# quadcopter.net
KiCad netlist of a schematic drawn in EAGLE
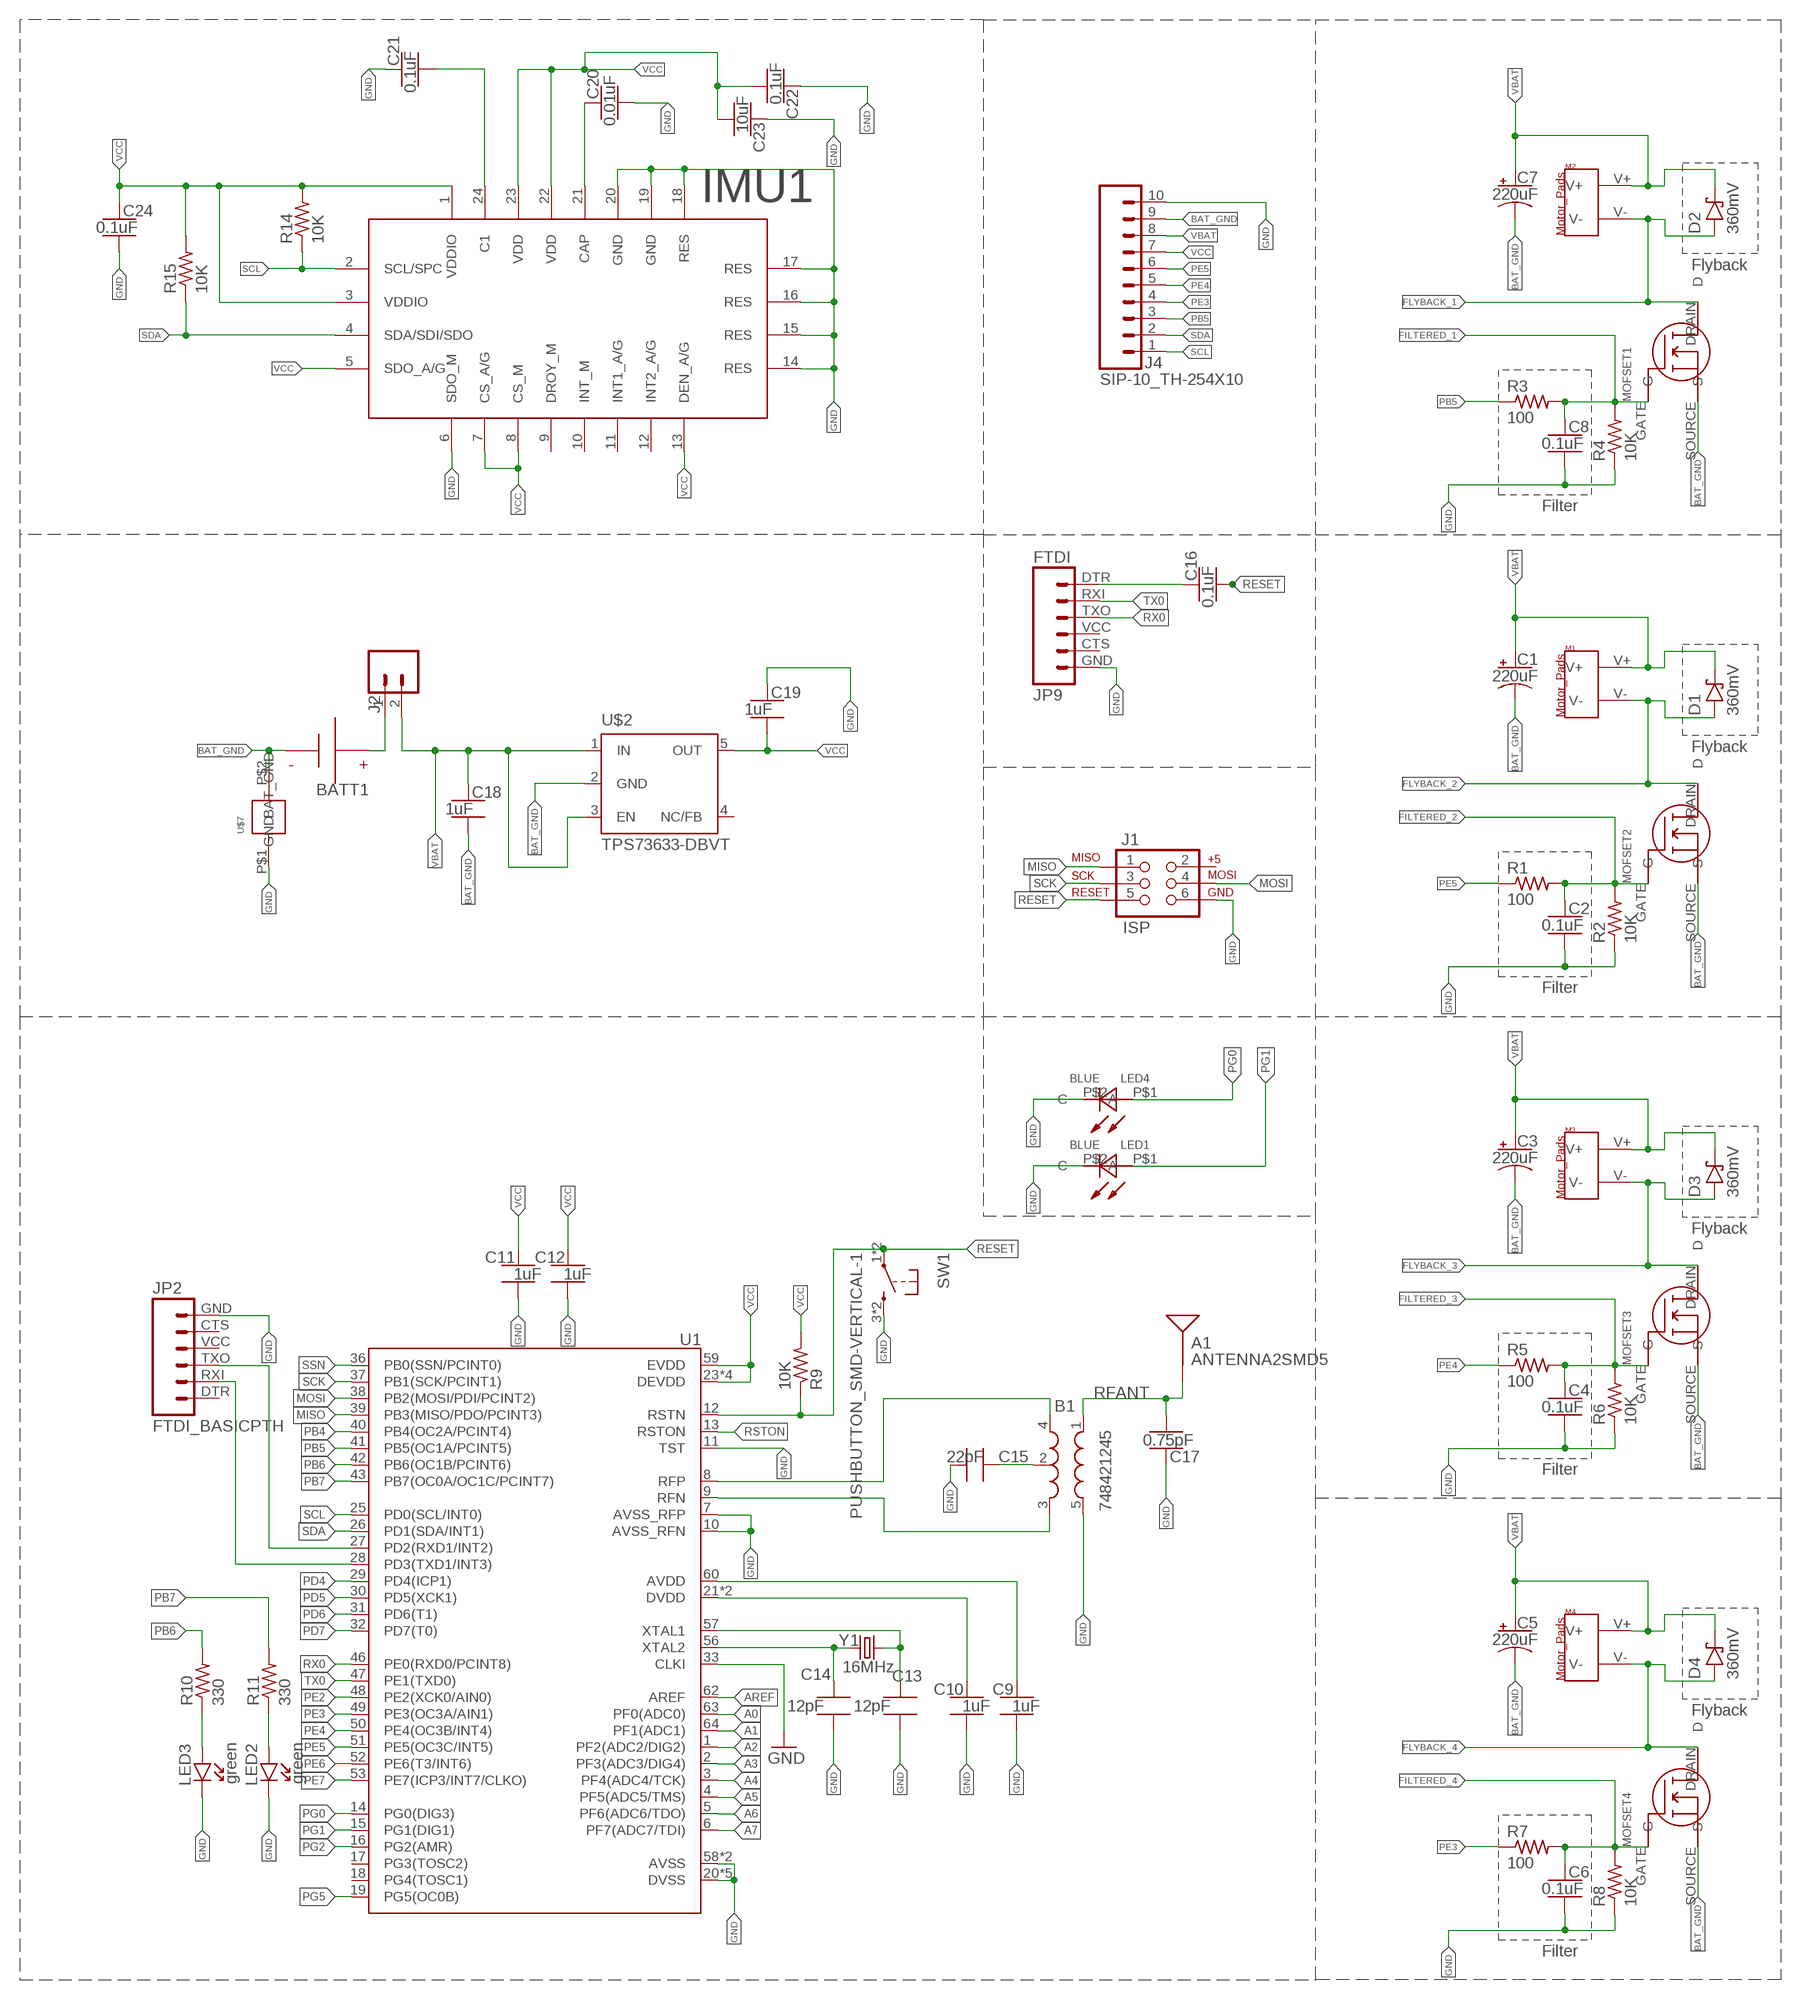
[diagram p0: schematic, sheet 1]

(export (version "E")
  (design (tool "Eeschema 10.0.6"))
  (components
    (comp (ref "A1")
      (value "ANTENNA2SMD5")
      (footprint "eagle-import:ANTENNA-CHIP5")
      (fields (field (name "MFR") "Linx Technologies Inc.") (field (name "MPN") "ANT-2.45-CHP-T"))
      (libsource (lib "eagle-import") (part "ANTENNA2SMD5"))
    )
    (comp (ref "B1")
      (value "748421245")
      (footprint "eagle-import:BALUN")
      (fields (field (name "MFR") "Wurth Electronics Inc") (field (name "CREATOR") "PROF"))
      (libsource (lib "eagle-import") (part "BALUN0805"))
    )
    (comp (ref "BATT1")
      (value "BATTERY-HUBSAN-W/HOLDER")
      (footprint "eagle-import:BATTERY-W_HOLDER-380MAH-HUBSAN")
      (fields
        (field (name "MFR") "HUBSAN")
        (field (name "MPN") "X4-H107C-8-in-1")
        (field (name "CREATOR") "Swanson")
      )
      (libsource (lib "eagle-import") (part "BATTERY-HUBSAN-W/HOLDER"))
    )
    (comp (ref "C1")
      (value "220uF")
      (footprint "eagle-import:CAPMP7343X310_HS")
      (fields (field (name "MFR") "AVX Corporation") (field (name "MPN") "TAJD227K006RNJ"))
      (libsource (lib "eagle-import") (part "CAPACITOR-POL_SMD-7043-D_TANTALUM-220UF"))
    )
    (comp (ref "C2")
      (value "0.1uF")
      (footprint "eagle-import:CAPC2012X140_HS")
      (fields
        (field (name "MFR") "Murata Electronics North America")
        (field (name "MPN") "GRM21BR71H104KA01L")
        (field (name "CREATOR") "PROF")
      )
      (libsource (lib "eagle-import") (part "CAPACITOR-NP_SMD-2012-0805_CERAMIC-0.1UF"))
    )
    (comp (ref "C3")
      (value "220uF")
      (footprint "eagle-import:CAPMP7343X310_HS")
      (fields (field (name "MFR") "AVX Corporation") (field (name "MPN") "TAJD227K006RNJ"))
      (libsource (lib "eagle-import") (part "CAPACITOR-POL_SMD-7043-D_TANTALUM-220UF"))
    )
    (comp (ref "C4")
      (value "0.1uF")
      (footprint "eagle-import:CAPC2012X140_HS")
      (fields
        (field (name "MFR") "Murata Electronics North America")
        (field (name "MPN") "GRM21BR71H104KA01L")
        (field (name "CREATOR") "PROF")
      )
      (libsource (lib "eagle-import") (part "CAPACITOR-NP_SMD-2012-0805_CERAMIC-0.1UF"))
    )
    (comp (ref "C5")
      (value "220uF")
      (footprint "eagle-import:CAPMP7343X310_HS")
      (fields (field (name "MFR") "AVX Corporation") (field (name "MPN") "TAJD227K006RNJ"))
      (libsource (lib "eagle-import") (part "CAPACITOR-POL_SMD-7043-D_TANTALUM-220UF"))
    )
    (comp (ref "C6")
      (value "0.1uF")
      (footprint "eagle-import:CAPC2012X140_HS")
      (fields
        (field (name "MFR") "Murata Electronics North America")
        (field (name "MPN") "GRM21BR71H104KA01L")
        (field (name "CREATOR") "PROF")
      )
      (libsource (lib "eagle-import") (part "CAPACITOR-NP_SMD-2012-0805_CERAMIC-0.1UF"))
    )
    (comp (ref "C7")
      (value "220uF")
      (footprint "eagle-import:CAPMP7343X310_HS")
      (fields (field (name "MFR") "AVX Corporation") (field (name "MPN") "TAJD227K006RNJ"))
      (libsource (lib "eagle-import") (part "CAPACITOR-POL_SMD-7043-D_TANTALUM-220UF"))
    )
    (comp (ref "C8")
      (value "0.1uF")
      (footprint "eagle-import:CAPC2012X140_HS")
      (fields
        (field (name "MFR") "Murata Electronics North America")
        (field (name "MPN") "GRM21BR71H104KA01L")
        (field (name "CREATOR") "PROF")
      )
      (libsource (lib "eagle-import") (part "CAPACITOR-NP_SMD-2012-0805_CERAMIC-0.1UF"))
    )
    (comp (ref "C9")
      (value "1uF")
      (footprint "eagle-import:CAPC2012X140_HS")
      (fields
        (field (name "MFR") "Murata Electronics North America")
        (field (name "MPN") "GRM21BR71H105KA12L")
      )
      (libsource (lib "eagle-import") (part "CAPACITOR-NP_SMD-2012-0805_CERAMIC-1UF"))
    )
    (comp (ref "C10")
      (value "1uF")
      (footprint "eagle-import:CAPC2012X140_HS")
      (fields
        (field (name "MFR") "Murata Electronics North America")
        (field (name "MPN") "GRM21BR71H105KA12L")
      )
      (libsource (lib "eagle-import") (part "CAPACITOR-NP_SMD-2012-0805_CERAMIC-1UF"))
    )
    (comp (ref "C11")
      (value "1uF")
      (footprint "eagle-import:CAPC2012X140_HS")
      (fields
        (field (name "MFR") "Murata Electronics North America")
        (field (name "MPN") "GRM21BR71H105KA12L")
      )
      (libsource (lib "eagle-import") (part "CAPACITOR-NP_SMD-2012-0805_CERAMIC-1UF"))
    )
    (comp (ref "C12")
      (value "1uF")
      (footprint "eagle-import:CAPC2012X140_HS")
      (fields
        (field (name "MFR") "Murata Electronics North America")
        (field (name "MPN") "GRM21BR71H105KA12L")
      )
      (libsource (lib "eagle-import") (part "CAPACITOR-NP_SMD-2012-0805_CERAMIC-1UF"))
    )
    (comp (ref "C13")
      (value "12pF")
      (footprint "eagle-import:CAPC2012X140_HS")
      (fields
        (field (name "MFR") "Murata Electronics North America")
        (field (name "MPN") "GRM21A5C2E120JW01D")
      )
      (libsource (lib "eagle-import") (part "CAPACITOR-NP_SMD-2012-0805_CERAMIC-12PF"))
    )
    (comp (ref "C14")
      (value "12pF")
      (footprint "eagle-import:CAPC2012X140_HS")
      (fields
        (field (name "MFR") "Murata Electronics North America")
        (field (name "MPN") "GRM21A5C2E120JW01D")
      )
      (libsource (lib "eagle-import") (part "CAPACITOR-NP_SMD-2012-0805_CERAMIC-12PF"))
    )
    (comp (ref "C15")
      (value "22pF")
      (footprint "eagle-import:CAPC2012X140_HS")
      (fields
        (field (name "MFR") "Murata Electronics North America")
        (field (name "MPN") "GRM21A5C2E220JW01D")
        (field (name "CREATOR") "PROF")
      )
      (libsource (lib "eagle-import") (part "CAPACITOR-NP_SMD-2012-0805_CERAMIC-22PF"))
    )
    (comp (ref "C16")
      (value "0.1uF")
      (footprint "eagle-import:CAPC2012X140_HS")
      (fields
        (field (name "MFR") "Murata Electronics North America")
        (field (name "MPN") "GRM21BR71H104KA01L")
        (field (name "CREATOR") "PROF")
      )
      (libsource (lib "eagle-import") (part "CAPACITOR-NP_SMD-2012-0805_CERAMIC-0.1UF"))
    )
    (comp (ref "C17")
      (value "0.75pF")
      (footprint "eagle-import:CAPC2012X140_HS")
      (fields
        (field (name "MFR") "Murata Electronics North America")
        (field (name "MPN") "GQM2195C2AR75CB01D")
      )
      (libsource (lib "eagle-import") (part "CAPACITOR-NP_SMD-2012-0805_CERAMIC-0.75PF"))
    )
    (comp (ref "C18")
      (value "1uF")
      (footprint "eagle-import:CAPC2012X140_HS")
      (fields
        (field (name "MFR") "Murata Electronics North America")
        (field (name "MPN") "GRM21BR71H105KA12L")
      )
      (libsource (lib "eagle-import") (part "CAPACITOR-NP_SMD-2012-0805_CERAMIC-1UF"))
    )
    (comp (ref "C19")
      (value "1uF")
      (footprint "eagle-import:CAPC2012X140_HS")
      (fields
        (field (name "MFR") "Murata Electronics North America")
        (field (name "MPN") "GRM21BR71H105KA12L")
      )
      (libsource (lib "eagle-import") (part "CAPACITOR-NP_SMD-2012-0805_CERAMIC-1UF"))
    )
    (comp (ref "C20")
      (value "0.01uF")
      (footprint "eagle-import:CAPC2012X140_HS")
      (fields
        (field (name "MFR") "Murata Electronics North America")
        (field (name "MPN") "GRM2195C1H103FA01D")
        (field (name "CREATOR") "PROF")
      )
      (libsource (lib "eagle-import") (part "CAPACITOR-NP_SMD-2012-0805_CERAMIC-0.01UF"))
    )
    (comp (ref "C21")
      (value "0.1uF")
      (footprint "eagle-import:CAPC2012X140_HS")
      (fields
        (field (name "MFR") "Murata Electronics North America")
        (field (name "MPN") "GRM21BR71H104KA01L")
        (field (name "CREATOR") "PROF")
      )
      (libsource (lib "eagle-import") (part "CAPACITOR-NP_SMD-2012-0805_CERAMIC-0.1UF"))
    )
    (comp (ref "C22")
      (value "0.1uF")
      (footprint "eagle-import:CAPC2012X140_HS")
      (fields
        (field (name "MFR") "Murata Electronics North America")
        (field (name "MPN") "GRM21BR71H104KA01L")
        (field (name "CREATOR") "PROF")
      )
      (libsource (lib "eagle-import") (part "CAPACITOR-NP_SMD-2012-0805_CERAMIC-0.1UF"))
    )
    (comp (ref "C23")
      (value "10uF")
      (footprint "eagle-import:CAPC2012X140_HS")
      (fields
        (field (name "MFR") "Murata Electronics North America")
        (field (name "MPN") "GRM21BR61E106KA73L")
      )
      (libsource (lib "eagle-import") (part "CAPACITOR-NP_SMD-2012-0805_CERAMIC-10UF"))
    )
    (comp (ref "C24")
      (value "0.1uF")
      (footprint "eagle-import:CAPC2012X140_HS")
      (fields
        (field (name "MFR") "Murata Electronics North America")
        (field (name "MPN") "GRM21BR71H104KA01L")
        (field (name "CREATOR") "PROF")
      )
      (libsource (lib "eagle-import") (part "CAPACITOR-NP_SMD-2012-0805_CERAMIC-0.1UF"))
    )
    (comp (ref "D1")
      (value "360mV")
      (footprint "eagle-import:SOD3716X135_HS")
      (fields
        (field (name "MFR") "Toshiba Semiconductor and Storage")
        (field (name "MPN") "CRS08(TE85L,Q,M)")
      )
      (libsource (lib "eagle-import") (part "DIODE-SCHOTTKY_SMD-SOD123-360MV"))
    )
    (comp (ref "D2")
      (value "360mV")
      (footprint "eagle-import:SOD3716X135_HS")
      (fields
        (field (name "MFR") "Toshiba Semiconductor and Storage")
        (field (name "MPN") "CRS08(TE85L,Q,M)")
      )
      (libsource (lib "eagle-import") (part "DIODE-SCHOTTKY_SMD-SOD123-360MV"))
    )
    (comp (ref "D3")
      (value "360mV")
      (footprint "eagle-import:SOD3716X135_HS")
      (fields
        (field (name "MFR") "Toshiba Semiconductor and Storage")
        (field (name "MPN") "CRS08(TE85L,Q,M)")
      )
      (libsource (lib "eagle-import") (part "DIODE-SCHOTTKY_SMD-SOD123-360MV"))
    )
    (comp (ref "D4")
      (value "360mV")
      (footprint "eagle-import:SOD3716X135_HS")
      (fields
        (field (name "MFR") "Toshiba Semiconductor and Storage")
        (field (name "MPN") "CRS08(TE85L,Q,M)")
      )
      (libsource (lib "eagle-import") (part "DIODE-SCHOTTKY_SMD-SOD123-360MV"))
    )
    (comp (ref "IMU1")
      (value "9_AXIS_IMU")
      (footprint "eagle-import:9_AXIS_IMU")
      (fields
        (field (name "MFR") "STMicroelectronics")
        (field (name "MPN") "LSM9DS1TR")
        (field (name "CREATOR") "Yupei")
        (field (name "REVIEWER") "Group 9")
      )
      (libsource (lib "eagle-import") (part "9_AXIS_IMU"))
    )
    (comp (ref "J1")
      (value "ISP")
      (footprint "eagle-import:2X3-NS")
      (fields
        (field (name "MFR") "Amphenol FCI")
        (field (name "MPN") "67997-206HLF")
        (field (name "CREATOR") "PROF")
      )
      (libsource (lib "eagle-import") (part "AVR_SPI_PRG_6NS"))
    )
    (comp (ref "J2")
      (value "MALE_HEADER_2POS-2X1-0.1IN")
      (footprint "eagle-import:MALE_HEADER_2X1_0.1IN")
      (fields
        (field (name "MFR") "3M")
        (field (name "MPN") "961102-6404-AR")
        (field (name "CREATOR") "SWANSON")
        (field (name "REVIEWER") "Group 9")
      )
      (libsource (lib "eagle-import") (part "MALE_HEADER_2POS-2X1-0.1IN"))
    )
    (comp (ref "J4")
      (value "SIP-10_TH-254X10")
      (footprint "eagle-import:HDRV10W63P254_10X1_2540X254H838_HS")
      (fields (field (name "MFR") "Amphenol FCI") (field (name "MPN") "68000-110HLF"))
      (libsource (lib "eagle-import") (part "SIP-10_TH-254X10"))
    )
    (comp (ref "JP2")
      (value "FTDI_BASICPTH")
      (footprint "eagle-import:FTDI_BASIC")
      (fields (field (name "MFR") "Amphenol FCI") (field (name "MPN") "68016-406HLF"))
      (libsource (lib "eagle-import") (part "FTDI_BASICPTH"))
    )
    (comp (ref "JP9")
      (value "FTDI")
      (footprint "eagle-import:FTDI_BASIC")
      (fields (field (name "MFR") "Amphenol FCI") (field (name "MPN") "68016-406HLF"))
      (libsource (lib "eagle-import") (part "FTDI_BASICPTH"))
    )
    (comp (ref "LED1")
      (value "BLUE")
      (footprint "eagle-import:CUT_TAPE")
      (fields
        (field (name "MFR") "Lite-On Inc ")
        (field (name "MPN") "LTST-C193TBKT-5A")
        (field (name "CREATOR") "Yueqi Wang")
        (field (name "REVIEWER") "Group 9")
      )
      (libsource (lib "eagle-import") (part "LTST-C193TBKT-5ADISCRETE_LED"))
    )
    (comp (ref "LED2")
      (value "green")
      (footprint "eagle-import:LEDSC125X200X120-2_HS")
      (fields (field (name "MFR") "Lite-On Inc") (field (name "MPN") "LTST-C170GKT"))
      (libsource (lib "eagle-import") (part "DIODE-LED_SMD-2012-0805-GREEN"))
    )
    (comp (ref "LED3")
      (value "green")
      (footprint "eagle-import:LEDSC125X200X120-2_HS")
      (fields (field (name "MFR") "Lite-On Inc") (field (name "MPN") "LTST-C170GKT"))
      (libsource (lib "eagle-import") (part "DIODE-LED_SMD-2012-0805-GREEN"))
    )
    (comp (ref "LED4")
      (value "BLUE")
      (footprint "eagle-import:CUT_TAPE")
      (fields
        (field (name "MFR") "Lite-On Inc ")
        (field (name "MPN") "LTST-C193TBKT-5A")
        (field (name "CREATOR") "Yueqi Wang")
        (field (name "REVIEWER") "Group 9")
      )
      (libsource (lib "eagle-import") (part "LTST-C193TBKT-5ADISCRETE_LED"))
    )
    (comp (ref "M1")
      (value "MOTOR_PADS")
      (footprint "eagle-import:MOTOR_PADS")
      (fields (field (name "MFR") "NA") (field (name "CREATOR") "PROF"))
      (libsource (lib "eagle-import") (part "MOTOR_PADS"))
    )
    (comp (ref "M2")
      (value "MOTOR_PADS")
      (footprint "eagle-import:MOTOR_PADS")
      (fields (field (name "MFR") "NA") (field (name "CREATOR") "PROF"))
      (libsource (lib "eagle-import") (part "MOTOR_PADS"))
    )
    (comp (ref "M3")
      (value "MOTOR_PADS")
      (footprint "eagle-import:MOTOR_PADS")
      (fields (field (name "MFR") "NA") (field (name "CREATOR") "PROF"))
      (libsource (lib "eagle-import") (part "MOTOR_PADS"))
    )
    (comp (ref "M4")
      (value "MOTOR_PADS")
      (footprint "eagle-import:MOTOR_PADS")
      (fields (field (name "MFR") "NA") (field (name "CREATOR") "PROF"))
      (libsource (lib "eagle-import") (part "MOTOR_PADS"))
    )
    (comp (ref "MOFSET1")
      (value "SI2302CDS_N_MOFSETSI2302CDS")
      (footprint "eagle-import:N-CHANNEL_MOSFET")
      (fields
        (field (name "MFR") "Vishay Siliconix ")
        (field (name "MPN") "SI2302CDS-T1-E3 ")
        (field (name "CREATOR") "YUEQI WANG")
        (field (name "REVIEWER") "Group 9")
      )
      (libsource (lib "eagle-import") (part "SI2302CDS_N_MOFSETSI2302CDS"))
    )
    (comp (ref "MOFSET2")
      (value "SI2302CDS_N_MOFSETSI2302CDS")
      (footprint "eagle-import:N-CHANNEL_MOSFET")
      (fields
        (field (name "MFR") "Vishay Siliconix ")
        (field (name "MPN") "SI2302CDS-T1-E3 ")
        (field (name "CREATOR") "YUEQI WANG")
        (field (name "REVIEWER") "Group 9")
      )
      (libsource (lib "eagle-import") (part "SI2302CDS_N_MOFSETSI2302CDS"))
    )
    (comp (ref "MOFSET3")
      (value "SI2302CDS_N_MOFSETSI2302CDS")
      (footprint "eagle-import:N-CHANNEL_MOSFET")
      (fields
        (field (name "MFR") "Vishay Siliconix ")
        (field (name "MPN") "SI2302CDS-T1-E3 ")
        (field (name "CREATOR") "YUEQI WANG")
        (field (name "REVIEWER") "Group 9")
      )
      (libsource (lib "eagle-import") (part "SI2302CDS_N_MOFSETSI2302CDS"))
    )
    (comp (ref "MOFSET4")
      (value "SI2302CDS_N_MOFSETSI2302CDS")
      (footprint "eagle-import:N-CHANNEL_MOSFET")
      (fields
        (field (name "MFR") "Vishay Siliconix ")
        (field (name "MPN") "SI2302CDS-T1-E3 ")
        (field (name "CREATOR") "YUEQI WANG")
        (field (name "REVIEWER") "Group 9")
      )
      (libsource (lib "eagle-import") (part "SI2302CDS_N_MOFSETSI2302CDS"))
    )
    (comp (ref "R1")
      (value "100")
      (footprint "eagle-import:RESC2012X60_HS")
      (fields
        (field (name "MFR") "Yageo")
        (field (name "MPN") "RC0805JR-07100RL")
        (field (name "CREATOR") "PROF")
      )
      (libsource (lib "eagle-import") (part "RESISTOR_SMD-2012-0805-100"))
    )
    (comp (ref "R2")
      (value "10K")
      (footprint "eagle-import:RESC2012X60_HS")
      (fields
        (field (name "MFR") "Yageo")
        (field (name "MPN") "RC0805JR-0710KL")
        (field (name "CREATOR") "PROF")
      )
      (libsource (lib "eagle-import") (part "RESISTOR_SMD-2012-0805-10K"))
    )
    (comp (ref "R3")
      (value "100")
      (footprint "eagle-import:RESC2012X60_HS")
      (fields
        (field (name "MFR") "Yageo")
        (field (name "MPN") "RC0805JR-07100RL")
        (field (name "CREATOR") "PROF")
      )
      (libsource (lib "eagle-import") (part "RESISTOR_SMD-2012-0805-100"))
    )
    (comp (ref "R4")
      (value "10K")
      (footprint "eagle-import:RESC2012X60_HS")
      (fields
        (field (name "MFR") "Yageo")
        (field (name "MPN") "RC0805JR-0710KL")
        (field (name "CREATOR") "PROF")
      )
      (libsource (lib "eagle-import") (part "RESISTOR_SMD-2012-0805-10K"))
    )
    (comp (ref "R5")
      (value "100")
      (footprint "eagle-import:RESC2012X60_HS")
      (fields
        (field (name "MFR") "Yageo")
        (field (name "MPN") "RC0805JR-07100RL")
        (field (name "CREATOR") "PROF")
      )
      (libsource (lib "eagle-import") (part "RESISTOR_SMD-2012-0805-100"))
    )
    (comp (ref "R6")
      (value "10K")
      (footprint "eagle-import:RESC2012X60_HS")
      (fields
        (field (name "MFR") "Yageo")
        (field (name "MPN") "RC0805JR-0710KL")
        (field (name "CREATOR") "PROF")
      )
      (libsource (lib "eagle-import") (part "RESISTOR_SMD-2012-0805-10K"))
    )
    (comp (ref "R7")
      (value "100")
      (footprint "eagle-import:RESC2012X60_HS")
      (fields
        (field (name "MFR") "Yageo")
        (field (name "MPN") "RC0805JR-07100RL")
        (field (name "CREATOR") "PROF")
      )
      (libsource (lib "eagle-import") (part "RESISTOR_SMD-2012-0805-100"))
    )
    (comp (ref "R8")
      (value "10K")
      (footprint "eagle-import:RESC2012X60_HS")
      (fields
        (field (name "MFR") "Yageo")
        (field (name "MPN") "RC0805JR-0710KL")
        (field (name "CREATOR") "PROF")
      )
      (libsource (lib "eagle-import") (part "RESISTOR_SMD-2012-0805-10K"))
    )
    (comp (ref "R9")
      (value "10K")
      (footprint "eagle-import:RESC2012X60_HS")
      (fields
        (field (name "MFR") "Yageo")
        (field (name "MPN") "RC0805JR-0710KL")
        (field (name "CREATOR") "PROF")
      )
      (libsource (lib "eagle-import") (part "RESISTOR_SMD-2012-0805-10K"))
    )
    (comp (ref "R10")
      (value "330")
      (footprint "eagle-import:RESC2012X60_HS")
      (fields
        (field (name "MFR") "Yageo")
        (field (name "MPN") "RC0805JR-07330RL")
        (field (name "CREATOR") "PROF")
      )
      (libsource (lib "eagle-import") (part "RESISTOR_SMD-2012-0805-330"))
    )
    (comp (ref "R11")
      (value "330")
      (footprint "eagle-import:RESC2012X60_HS")
      (fields
        (field (name "MFR") "Yageo")
        (field (name "MPN") "RC0805JR-07330RL")
        (field (name "CREATOR") "PROF")
      )
      (libsource (lib "eagle-import") (part "RESISTOR_SMD-2012-0805-330"))
    )
    (comp (ref "R14")
      (value "10K")
      (footprint "eagle-import:RESC2012X60_HS")
      (fields
        (field (name "MFR") "Yageo")
        (field (name "MPN") "RC0805JR-0710KL")
        (field (name "CREATOR") "PROF")
      )
      (libsource (lib "eagle-import") (part "RESISTOR_SMD-2012-0805-10K"))
    )
    (comp (ref "R15")
      (value "10K")
      (footprint "eagle-import:RESC2012X60_HS")
      (fields
        (field (name "MFR") "Yageo")
        (field (name "MPN") "RC0805JR-0710KL")
        (field (name "CREATOR") "PROF")
      )
      (libsource (lib "eagle-import") (part "RESISTOR_SMD-2012-0805-10K"))
    )
    (comp (ref "SW1")
      (value "PUSHBUTTON_SMD-VERTICAL-1")
      (footprint "eagle-import:TE_FSM8JSMA_HS")
      (fields (field (name "MFR") "TE Connectivity Alcoswitch Switches") (field (name "MPN") "FSM4JSMA"))
      (libsource (lib "eagle-import") (part "PUSHBUTTON_SMD-VERTICAL-1"))
    )
    (comp (ref "U$2")
      (value "TPS73633-DBVT")
      (footprint "eagle-import:SOT23-DBV")
      (fields (field (name "MFR") "Texas Instruments") (field (name "MPN") "LP3985IM5X-3.0/NOPB"))
      (libsource (lib "eagle-import") (part "TPS73633-DBVT"))
    )
    (comp (ref "U$7")
      (value "NET_BRIDGE")
      (footprint "eagle-import:NET_BRIDGE")
      (libsource (lib "eagle-import") (part "NET_BRIDGE"))
    )
    (comp (ref "U1")
      (value "ATMEGA128RFA1")
      (footprint "eagle-import:QFN-64")
      (fields
        (field (name "MFR") "Atmel")
        (field (name "MPN") "ATMEGA128RFA1-ZUR00")
        (field (name "CREATOR") "Swanson")
      )
      (libsource (lib "eagle-import") (part "ATMEGA128RFA1"))
    )
    (comp (ref "Y1")
      (value "16MHz")
      (footprint "eagle-import:CRYSTAL-SMD-5X3")
      (fields (field (name "MFR") "Abracon LLC") (field (name "MPN") "ABM3B-16.000MHZ-B2-T"))
      (libsource (lib "eagle-import") (part "CRYSTAL5X3"))
    )
  )
  (nets
    (net (code "1") (name "/RFANT") (class "Default")
      (node (ref "A1") (pin "FEED") (pinfunction "SIGNAL_FEED") (pintype "bidirectional"))
      (node (ref "B1") (pin "1") (pinfunction "IN_1") (pintype "bidirectional"))
      (node (ref "C17") (pin "2") (pinfunction "2_2") (pintype "passive"))
    )
    (net (code "2") (name "A0") (class "Default")
      (node (ref "U1") (pin "63") (pinfunction "PF0(ADC0)_63") (pintype "bidirectional"))
    )
    (net (code "3") (name "A1") (class "Default")
      (node (ref "U1") (pin "64") (pinfunction "PF1(ADC1)_64") (pintype "bidirectional"))
    )
    (net (code "4") (name "A2") (class "Default")
      (node (ref "U1") (pin "1") (pinfunction "PF2(ADC2/DIG2)_1") (pintype "bidirectional"))
    )
    (net (code "5") (name "A3") (class "Default")
      (node (ref "U1") (pin "2") (pinfunction "PF3(ADC3/DIG4)_2") (pintype "bidirectional"))
    )
    (net (code "6") (name "A4") (class "Default")
      (node (ref "U1") (pin "3") (pinfunction "PF4(ADC4/TCK)_3") (pintype "bidirectional"))
    )
    (net (code "7") (name "A5") (class "Default")
      (node (ref "U1") (pin "4") (pinfunction "PF5(ADC5/TMS)_4") (pintype "bidirectional"))
    )
    (net (code "8") (name "A6") (class "Default")
      (node (ref "U1") (pin "5") (pinfunction "PF6(ADC6/TDO)_5") (pintype "bidirectional"))
    )
    (net (code "9") (name "A7") (class "Default")
      (node (ref "U1") (pin "6") (pinfunction "PF7(ADC7/TDI)_6") (pintype "bidirectional"))
    )
    (net (code "10") (name "AREF") (class "Default")
      (node (ref "U1") (pin "62") (pinfunction "AREF_62") (pintype "bidirectional"))
    )
    (net (code "11") (name "BAT_GND") (class "Default")
      (node (ref "BATT1") (pin "-") (pinfunction "N_-") (pintype "bidirectional"))
      (node (ref "C1") (pin "2") (pinfunction "-_2") (pintype "passive"))
      (node (ref "C18") (pin "2") (pinfunction "2_2") (pintype "passive"))
      (node (ref "C3") (pin "2") (pinfunction "-_2") (pintype "passive"))
      (node (ref "C5") (pin "2") (pinfunction "-_2") (pintype "passive"))
      (node (ref "C7") (pin "2") (pinfunction "-_2") (pintype "passive"))
      (node (ref "J4") (pin "9") (pinfunction "9_9") (pintype "passive"))
      (node (ref "MOFSET1") (pin "SOURCE") (pinfunction "S_SOURCE") (pintype "bidirectional"))
      (node (ref "MOFSET2") (pin "SOURCE") (pinfunction "S_SOURCE") (pintype "bidirectional"))
      (node (ref "MOFSET3") (pin "SOURCE") (pinfunction "S_SOURCE") (pintype "bidirectional"))
      (node (ref "MOFSET4") (pin "SOURCE") (pinfunction "S_SOURCE") (pintype "bidirectional"))
      (node (ref "U$2") (pin "2") (pinfunction "GND_2") (pintype "input"))
      (node (ref "U$7") (pin "P$2") (pinfunction "GND_P$2") (pintype "bidirectional"))
    )
    (net (code "12") (name "FILTERED_1") (class "Default")
      (node (ref "C8") (pin "1") (pinfunction "1_1") (pintype "passive"))
      (node (ref "MOFSET1") (pin "GATE") (pinfunction "G_GATE") (pintype "bidirectional"))
      (node (ref "R3") (pin "2") (pinfunction "2_2") (pintype "passive"))
      (node (ref "R4") (pin "2") (pinfunction "2_2") (pintype "passive"))
    )
    (net (code "13") (name "FILTERED_2") (class "Default")
      (node (ref "C2") (pin "1") (pinfunction "1_1") (pintype "passive"))
      (node (ref "MOFSET2") (pin "GATE") (pinfunction "G_GATE") (pintype "bidirectional"))
      (node (ref "R1") (pin "2") (pinfunction "2_2") (pintype "passive"))
      (node (ref "R2") (pin "2") (pinfunction "2_2") (pintype "passive"))
    )
    (net (code "14") (name "FILTERED_3") (class "Default")
      (node (ref "C4") (pin "1") (pinfunction "1_1") (pintype "passive"))
      (node (ref "MOFSET3") (pin "GATE") (pinfunction "G_GATE") (pintype "bidirectional"))
      (node (ref "R5") (pin "2") (pinfunction "2_2") (pintype "passive"))
      (node (ref "R6") (pin "2") (pinfunction "2_2") (pintype "passive"))
    )
    (net (code "15") (name "FILTERED_4") (class "Default")
      (node (ref "C6") (pin "1") (pinfunction "1_1") (pintype "passive"))
      (node (ref "MOFSET4") (pin "GATE") (pinfunction "G_GATE") (pintype "bidirectional"))
      (node (ref "R7") (pin "2") (pinfunction "2_2") (pintype "passive"))
      (node (ref "R8") (pin "2") (pinfunction "2_2") (pintype "passive"))
    )
    (net (code "16") (name "FLYBACK_1") (class "Default")
      (node (ref "D2") (pin "A") (pinfunction "A_A") (pintype "passive"))
      (node (ref "M2") (pin "V-") (pinfunction "V-_V-") (pintype "bidirectional"))
      (node (ref "MOFSET1") (pin "DRAIN") (pinfunction "D_DRAIN") (pintype "bidirectional"))
    )
    (net (code "17") (name "FLYBACK_2") (class "Default")
      (node (ref "D1") (pin "A") (pinfunction "A_A") (pintype "passive"))
      (node (ref "M1") (pin "V-") (pinfunction "V-_V-") (pintype "bidirectional"))
      (node (ref "MOFSET2") (pin "DRAIN") (pinfunction "D_DRAIN") (pintype "bidirectional"))
    )
    (net (code "18") (name "FLYBACK_3") (class "Default")
      (node (ref "D3") (pin "A") (pinfunction "A_A") (pintype "passive"))
      (node (ref "M3") (pin "V-") (pinfunction "V-_V-") (pintype "bidirectional"))
      (node (ref "MOFSET3") (pin "DRAIN") (pinfunction "D_DRAIN") (pintype "bidirectional"))
    )
    (net (code "19") (name "FLYBACK_4") (class "Default")
      (node (ref "D4") (pin "A") (pinfunction "A_A") (pintype "passive"))
      (node (ref "M4") (pin "V-") (pinfunction "V-_V-") (pintype "bidirectional"))
      (node (ref "MOFSET4") (pin "DRAIN") (pinfunction "D_DRAIN") (pintype "bidirectional"))
    )
    (net (code "20") (name "GND") (class "Default")
      (node (ref "B1") (pin "5") (pinfunction "GND_5") (pintype "bidirectional"))
      (node (ref "C10") (pin "2") (pinfunction "2_2") (pintype "passive"))
      (node (ref "C11") (pin "2") (pinfunction "2_2") (pintype "passive"))
      (node (ref "C12") (pin "2") (pinfunction "2_2") (pintype "passive"))
      (node (ref "C13") (pin "2") (pinfunction "2_2") (pintype "passive"))
      (node (ref "C14") (pin "2") (pinfunction "2_2") (pintype "passive"))
      (node (ref "C15") (pin "2") (pinfunction "2_2") (pintype "passive"))
      (node (ref "C17") (pin "1") (pinfunction "1_1") (pintype "passive"))
      (node (ref "C19") (pin "1") (pinfunction "1_1") (pintype "passive"))
      (node (ref "C2") (pin "2") (pinfunction "2_2") (pintype "passive"))
      (node (ref "C20") (pin "2") (pinfunction "2_2") (pintype "passive"))
      (node (ref "C21") (pin "1") (pinfunction "1_1") (pintype "passive"))
      (node (ref "C22") (pin "1") (pinfunction "1_1") (pintype "passive"))
      (node (ref "C23") (pin "1") (pinfunction "1_1") (pintype "passive"))
      (node (ref "C24") (pin "2") (pinfunction "2_2") (pintype "passive"))
      (node (ref "C4") (pin "2") (pinfunction "2_2") (pintype "passive"))
      (node (ref "C6") (pin "2") (pinfunction "2_2") (pintype "passive"))
      (node (ref "C8") (pin "2") (pinfunction "2_2") (pintype "passive"))
      (node (ref "C9") (pin "2") (pinfunction "2_2") (pintype "passive"))
      (node (ref "IMU1") (pin "14") (pinfunction "RES_14") (pintype "bidirectional"))
      (node (ref "IMU1") (pin "15") (pinfunction "RES_15") (pintype "bidirectional"))
      (node (ref "IMU1") (pin "16") (pinfunction "RES_16") (pintype "bidirectional"))
      (node (ref "IMU1") (pin "17") (pinfunction "RES_17") (pintype "bidirectional"))
      (node (ref "IMU1") (pin "18") (pinfunction "RES_18") (pintype "bidirectional"))
      (node (ref "IMU1") (pin "19") (pinfunction "GND_19") (pintype "bidirectional"))
      (node (ref "IMU1") (pin "20") (pinfunction "GND_20") (pintype "bidirectional"))
      (node (ref "IMU1") (pin "6") (pinfunction "SDO_M_6") (pintype "bidirectional"))
      (node (ref "J1") (pin "6") (pinfunction "6_6") (pintype "passive"))
      (node (ref "J4") (pin "10") (pinfunction "10_10") (pintype "passive"))
      (node (ref "JP2") (pin "GND") (pinfunction "6_GND") (pintype "passive"))
      (node (ref "JP9") (pin "GND") (pinfunction "6_GND") (pintype "passive"))
      (node (ref "LED1") (pin "P$2") (pinfunction "C_P$2") (pintype "bidirectional"))
      (node (ref "LED2") (pin "C") (pinfunction "C_C") (pintype "passive"))
      (node (ref "LED3") (pin "C") (pinfunction "C_C") (pintype "passive"))
      (node (ref "LED4") (pin "P$2") (pinfunction "C_P$2") (pintype "bidirectional"))
      (node (ref "R2") (pin "1") (pinfunction "1_1") (pintype "passive"))
      (node (ref "R4") (pin "1") (pinfunction "1_1") (pintype "passive"))
      (node (ref "R6") (pin "1") (pinfunction "1_1") (pintype "passive"))
      (node (ref "R8") (pin "1") (pinfunction "1_1") (pintype "passive"))
      (node (ref "SW1") (pin "3") (pinfunction "2_3") (pintype "passive"))
      (node (ref "SW1") (pin "4") (pinfunction "2_4") (pintype "passive"))
      (node (ref "U$7") (pin "P$1") (pinfunction "BAT_GND_P$1") (pintype "bidirectional"))
      (node (ref "U1") (pin "10") (pinfunction "AVSS_RFN_10") (pintype "bidirectional"))
      (node (ref "U1") (pin "11") (pinfunction "TST_11") (pintype "bidirectional"))
      (node (ref "U1") (pin "20") (pinfunction "DVSS_20") (pintype "bidirectional"))
      (node (ref "U1") (pin "24") (pinfunction "DVSS_24") (pintype "bidirectional"))
      (node (ref "U1") (pin "33") (pinfunction "CLKI_33") (pintype "bidirectional"))
      (node (ref "U1") (pin "35") (pinfunction "DVSS_35") (pintype "bidirectional"))
      (node (ref "U1") (pin "45") (pinfunction "DVSS_45") (pintype "bidirectional"))
      (node (ref "U1") (pin "55") (pinfunction "DVSS_55") (pintype "bidirectional"))
      (node (ref "U1") (pin "58") (pinfunction "AVSS_58") (pintype "bidirectional"))
      (node (ref "U1") (pin "61") (pinfunction "AVSS_61") (pintype "bidirectional"))
      (node (ref "U1") (pin "7") (pinfunction "AVSS_RFP_7") (pintype "bidirectional"))
    )
    (net (code "21") (name "MISO") (class "Default")
      (node (ref "J1") (pin "1") (pinfunction "1_1") (pintype "passive"))
      (node (ref "U1") (pin "39") (pinfunction "PB3(MISO/PDO/PCINT3)_39") (pintype "bidirectional"))
    )
    (net (code "22") (name "MOSI") (class "Default")
      (node (ref "J1") (pin "4") (pinfunction "4_4") (pintype "passive"))
      (node (ref "U1") (pin "38") (pinfunction "PB2(MOSI/PDI/PCINT2)_38") (pintype "bidirectional"))
    )
    (net (code "23") (name "Net-(B1-GND-Pad2)") (class "Default")
      (node (ref "B1") (pin "2") (pinfunction "GND_2") (pintype "bidirectional"))
      (node (ref "C15") (pin "1") (pinfunction "1_1") (pintype "passive"))
    )
    (net (code "24") (name "Net-(B1-OUT1)") (class "Default")
      (node (ref "B1") (pin "4") (pinfunction "OUT1_4") (pintype "bidirectional"))
      (node (ref "U1") (pin "8") (pinfunction "RFP_8") (pintype "bidirectional"))
    )
    (net (code "25") (name "Net-(B1-OUT2)") (class "Default")
      (node (ref "B1") (pin "3") (pinfunction "OUT2_3") (pintype "bidirectional"))
      (node (ref "U1") (pin "9") (pinfunction "RFN_9") (pintype "bidirectional"))
    )
    (net (code "26") (name "Net-(BATT1-P)") (class "Default")
      (node (ref "BATT1") (pin "+") (pinfunction "P_+") (pintype "bidirectional"))
      (node (ref "J2") (pin "1") (pinfunction "1_1") (pintype "passive"))
    )
    (net (code "27") (name "Net-(C10-Pad1)") (class "Default")
      (node (ref "C10") (pin "1") (pinfunction "1_1") (pintype "passive"))
      (node (ref "U1") (pin "21") (pinfunction "DVDD_21") (pintype "bidirectional"))
      (node (ref "U1") (pin "22") (pinfunction "DVDD_22") (pintype "bidirectional"))
    )
    (net (code "28") (name "Net-(IMU1-C1)") (class "Default")
      (node (ref "C21") (pin "2") (pinfunction "2_2") (pintype "passive"))
      (node (ref "IMU1") (pin "24") (pinfunction "C1_24") (pintype "bidirectional"))
    )
    (net (code "29") (name "Net-(IMU1-CAP)") (class "Default")
      (node (ref "C20") (pin "1") (pinfunction "1_1") (pintype "passive"))
      (node (ref "IMU1") (pin "21") (pinfunction "CAP_21") (pintype "bidirectional"))
    )
    (net (code "30") (name "Net-(JP2-2)") (class "Default")
      (node (ref "JP2") (pin "RXI") (pinfunction "2_RXI") (pintype "passive"))
      (node (ref "U1") (pin "28") (pinfunction "PD3(TXD1/INT3)_28") (pintype "bidirectional"))
    )
    (net (code "31") (name "Net-(JP2-3)") (class "Default")
      (node (ref "JP2") (pin "TXO") (pinfunction "3_TXO") (pintype "passive"))
      (node (ref "U1") (pin "27") (pinfunction "PD2(RXD1/INT2)_27") (pintype "bidirectional"))
    )
    (net (code "32") (name "Net-(JP9-1)") (class "Default")
      (node (ref "C16") (pin "1") (pinfunction "1_1") (pintype "passive"))
      (node (ref "JP9") (pin "DTR") (pinfunction "1_DTR") (pintype "passive"))
    )
    (net (code "33") (name "Net-(LED2-PadA)") (class "Default")
      (node (ref "LED2") (pin "A") (pinfunction "A_A") (pintype "passive"))
      (node (ref "R11") (pin "1") (pinfunction "1_1") (pintype "passive"))
    )
    (net (code "34") (name "Net-(LED3-PadA)") (class "Default")
      (node (ref "LED3") (pin "A") (pinfunction "A_A") (pintype "passive"))
      (node (ref "R10") (pin "1") (pinfunction "1_1") (pintype "passive"))
    )
    (net (code "35") (name "Net-(U1-AVDD)") (class "Default")
      (node (ref "C9") (pin "1") (pinfunction "1_1") (pintype "passive"))
      (node (ref "U1") (pin "60") (pinfunction "AVDD_60") (pintype "bidirectional"))
    )
    (net (code "36") (name "Net-(U1-XTAL1)") (class "Default")
      (node (ref "C13") (pin "1") (pinfunction "1_1") (pintype "passive"))
      (node (ref "U1") (pin "57") (pinfunction "XTAL1_57") (pintype "bidirectional"))
      (node (ref "Y1") (pin "3") (pinfunction "2_3") (pintype "passive"))
    )
    (net (code "37") (name "Net-(U1-XTAL2)") (class "Default")
      (node (ref "C14") (pin "1") (pinfunction "1_1") (pintype "passive"))
      (node (ref "U1") (pin "56") (pinfunction "XTAL2_56") (pintype "bidirectional"))
      (node (ref "Y1") (pin "1") (pinfunction "1_1") (pintype "passive"))
    )
    (net (code "38") (name "PB4") (class "Default")
      (node (ref "U1") (pin "40") (pinfunction "PB4(OC2A/PCINT4)_40") (pintype "bidirectional"))
    )
    (net (code "39") (name "PB5") (class "Default")
      (node (ref "J4") (pin "3") (pinfunction "3_3") (pintype "passive"))
      (node (ref "R3") (pin "1") (pinfunction "1_1") (pintype "passive"))
      (node (ref "U1") (pin "41") (pinfunction "PB5(OC1A/PCINT5)_41") (pintype "bidirectional"))
    )
    (net (code "40") (name "PB6") (class "Default")
      (node (ref "R10") (pin "2") (pinfunction "2_2") (pintype "passive"))
      (node (ref "U1") (pin "42") (pinfunction "PB6(OC1B/PCINT6)_42") (pintype "bidirectional"))
    )
    (net (code "41") (name "PB7") (class "Default")
      (node (ref "R11") (pin "2") (pinfunction "2_2") (pintype "passive"))
      (node (ref "U1") (pin "43") (pinfunction "PB7(OC0A/OC1C/PCINT7)_43") (pintype "bidirectional"))
    )
    (net (code "42") (name "PD4") (class "Default")
      (node (ref "U1") (pin "29") (pinfunction "PD4(ICP1)_29") (pintype "bidirectional"))
    )
    (net (code "43") (name "PD5") (class "Default")
      (node (ref "U1") (pin "30") (pinfunction "PD5(XCK1)_30") (pintype "bidirectional"))
    )
    (net (code "44") (name "PD6") (class "Default")
      (node (ref "U1") (pin "31") (pinfunction "PD6(T1)_31") (pintype "bidirectional"))
    )
    (net (code "45") (name "PD7") (class "Default")
      (node (ref "U1") (pin "32") (pinfunction "PD7(T0)_32") (pintype "bidirectional"))
    )
    (net (code "46") (name "PE2") (class "Default")
      (node (ref "U1") (pin "48") (pinfunction "PE2(XCK0/AIN0)_48") (pintype "bidirectional"))
    )
    (net (code "47") (name "PE3") (class "Default")
      (node (ref "J4") (pin "4") (pinfunction "4_4") (pintype "passive"))
      (node (ref "R7") (pin "1") (pinfunction "1_1") (pintype "passive"))
      (node (ref "U1") (pin "49") (pinfunction "PE3(OC3A/AIN1)_49") (pintype "bidirectional"))
    )
    (net (code "48") (name "PE4") (class "Default")
      (node (ref "J4") (pin "5") (pinfunction "5_5") (pintype "passive"))
      (node (ref "R5") (pin "1") (pinfunction "1_1") (pintype "passive"))
      (node (ref "U1") (pin "50") (pinfunction "PE4(OC3B/INT4)_50") (pintype "bidirectional"))
    )
    (net (code "49") (name "PE5") (class "Default")
      (node (ref "J4") (pin "6") (pinfunction "6_6") (pintype "passive"))
      (node (ref "R1") (pin "1") (pinfunction "1_1") (pintype "passive"))
      (node (ref "U1") (pin "51") (pinfunction "PE5(OC3C/INT5)_51") (pintype "bidirectional"))
    )
    (net (code "50") (name "PE6") (class "Default")
      (node (ref "U1") (pin "52") (pinfunction "PE6(T3/INT6)_52") (pintype "bidirectional"))
    )
    (net (code "51") (name "PE7") (class "Default")
      (node (ref "U1") (pin "53") (pinfunction "PE7(ICP3/INT7/CLKO)_53") (pintype "bidirectional"))
    )
    (net (code "52") (name "PG0") (class "Default")
      (node (ref "LED4") (pin "P$1") (pinfunction "A_P$1") (pintype "bidirectional"))
      (node (ref "U1") (pin "14") (pinfunction "PG0(DIG3)_14") (pintype "bidirectional"))
    )
    (net (code "53") (name "PG1") (class "Default")
      (node (ref "LED1") (pin "P$1") (pinfunction "A_P$1") (pintype "bidirectional"))
      (node (ref "U1") (pin "15") (pinfunction "PG1(DIG1)_15") (pintype "bidirectional"))
    )
    (net (code "54") (name "PG2") (class "Default")
      (node (ref "U1") (pin "16") (pinfunction "PG2(AMR)_16") (pintype "bidirectional"))
    )
    (net (code "55") (name "PG5") (class "Default")
      (node (ref "U1") (pin "19") (pinfunction "PG5(OC0B)_19") (pintype "bidirectional"))
    )
    (net (code "56") (name "RESET") (class "Default")
      (node (ref "C16") (pin "2") (pinfunction "2_2") (pintype "passive"))
      (node (ref "J1") (pin "5") (pinfunction "5_5") (pintype "passive"))
      (node (ref "R9") (pin "1") (pinfunction "1_1") (pintype "passive"))
      (node (ref "SW1") (pin "1") (pinfunction "1_1") (pintype "passive"))
      (node (ref "SW1") (pin "2") (pinfunction "1_2") (pintype "passive"))
      (node (ref "U1") (pin "12") (pinfunction "RSTN_12") (pintype "bidirectional"))
    )
    (net (code "57") (name "RSTON") (class "Default")
      (node (ref "U1") (pin "13") (pinfunction "RSTON_13") (pintype "bidirectional"))
    )
    (net (code "58") (name "RX0") (class "Default")
      (node (ref "JP9") (pin "TXO") (pinfunction "3_TXO") (pintype "passive"))
      (node (ref "U1") (pin "46") (pinfunction "PE0(RXD0/PCINT8)_46") (pintype "bidirectional"))
    )
    (net (code "59") (name "SCK") (class "Default")
      (node (ref "J1") (pin "3") (pinfunction "3_3") (pintype "passive"))
      (node (ref "U1") (pin "37") (pinfunction "PB1(SCK/PCINT1)_37") (pintype "bidirectional"))
    )
    (net (code "60") (name "SCL") (class "Default")
      (node (ref "IMU1") (pin "2") (pinfunction "SCL/SPC_2") (pintype "bidirectional"))
      (node (ref "J4") (pin "1") (pinfunction "1_1") (pintype "passive"))
      (node (ref "R14") (pin "1") (pinfunction "1_1") (pintype "passive"))
      (node (ref "U1") (pin "25") (pinfunction "PD0(SCL/INT0)_25") (pintype "bidirectional"))
    )
    (net (code "61") (name "SDA") (class "Default")
      (node (ref "IMU1") (pin "4") (pinfunction "SDA/SDI/SDO_4") (pintype "bidirectional"))
      (node (ref "J4") (pin "2") (pinfunction "2_2") (pintype "passive"))
      (node (ref "R15") (pin "1") (pinfunction "1_1") (pintype "passive"))
      (node (ref "U1") (pin "26") (pinfunction "PD1(SDA/INT1)_26") (pintype "bidirectional"))
    )
    (net (code "62") (name "SSN") (class "Default")
      (node (ref "U1") (pin "36") (pinfunction "PB0(SSN/PCINT0)_36") (pintype "bidirectional"))
    )
    (net (code "63") (name "TX0") (class "Default")
      (node (ref "JP9") (pin "RXI") (pinfunction "2_RXI") (pintype "passive"))
      (node (ref "U1") (pin "47") (pinfunction "PE1(TXD0)_47") (pintype "bidirectional"))
    )
    (net (code "64") (name "VBAT") (class "Default")
      (node (ref "C1") (pin "1") (pinfunction "+_1") (pintype "passive"))
      (node (ref "C18") (pin "1") (pinfunction "1_1") (pintype "passive"))
      (node (ref "C3") (pin "1") (pinfunction "+_1") (pintype "passive"))
      (node (ref "C5") (pin "1") (pinfunction "+_1") (pintype "passive"))
      (node (ref "C7") (pin "1") (pinfunction "+_1") (pintype "passive"))
      (node (ref "D1") (pin "C") (pinfunction "C_C") (pintype "passive"))
      (node (ref "D2") (pin "C") (pinfunction "C_C") (pintype "passive"))
      (node (ref "D3") (pin "C") (pinfunction "C_C") (pintype "passive"))
      (node (ref "D4") (pin "C") (pinfunction "C_C") (pintype "passive"))
      (node (ref "J2") (pin "2") (pinfunction "2_2") (pintype "passive"))
      (node (ref "J4") (pin "8") (pinfunction "8_8") (pintype "passive"))
      (node (ref "M1") (pin "V+") (pinfunction "V+_V+") (pintype "bidirectional"))
      (node (ref "M2") (pin "V+") (pinfunction "V+_V+") (pintype "bidirectional"))
      (node (ref "M3") (pin "V+") (pinfunction "V+_V+") (pintype "bidirectional"))
      (node (ref "M4") (pin "V+") (pinfunction "V+_V+") (pintype "bidirectional"))
      (node (ref "U$2") (pin "1") (pinfunction "IN_1") (pintype "input"))
      (node (ref "U$2") (pin "3") (pinfunction "EN_3") (pintype "input"))
    )
    (net (code "65") (name "VCC") (class "Default")
      (node (ref "C11") (pin "1") (pinfunction "1_1") (pintype "passive"))
      (node (ref "C12") (pin "1") (pinfunction "1_1") (pintype "passive"))
      (node (ref "C19") (pin "2") (pinfunction "2_2") (pintype "passive"))
      (node (ref "C22") (pin "2") (pinfunction "2_2") (pintype "passive"))
      (node (ref "C23") (pin "2") (pinfunction "2_2") (pintype "passive"))
      (node (ref "C24") (pin "1") (pinfunction "1_1") (pintype "passive"))
      (node (ref "IMU1") (pin "1") (pinfunction "VDDIO_1") (pintype "bidirectional"))
      (node (ref "IMU1") (pin "13") (pinfunction "DEN_A/G_13") (pintype "bidirectional"))
      (node (ref "IMU1") (pin "22") (pinfunction "VDD_22") (pintype "bidirectional"))
      (node (ref "IMU1") (pin "23") (pinfunction "VDD_23") (pintype "bidirectional"))
      (node (ref "IMU1") (pin "3") (pinfunction "VDDIO_3") (pintype "bidirectional"))
      (node (ref "IMU1") (pin "5") (pinfunction "SDO_A/G_5") (pintype "bidirectional"))
      (node (ref "IMU1") (pin "7") (pinfunction "CS_A/G_7") (pintype "bidirectional"))
      (node (ref "IMU1") (pin "8") (pinfunction "CS_M_8") (pintype "bidirectional"))
      (node (ref "J4") (pin "7") (pinfunction "7_7") (pintype "passive"))
      (node (ref "R14") (pin "2") (pinfunction "2_2") (pintype "passive"))
      (node (ref "R15") (pin "2") (pinfunction "2_2") (pintype "passive"))
      (node (ref "R9") (pin "2") (pinfunction "2_2") (pintype "passive"))
      (node (ref "U$2") (pin "5") (pinfunction "OUT_5") (pintype "passive"))
      (node (ref "U1") (pin "23") (pinfunction "DEVDD_23") (pintype "bidirectional"))
      (node (ref "U1") (pin "34") (pinfunction "DEVDD_34") (pintype "bidirectional"))
      (node (ref "U1") (pin "44") (pinfunction "DEVDD_44") (pintype "bidirectional"))
      (node (ref "U1") (pin "54") (pinfunction "DEVDD_54") (pintype "bidirectional"))
      (node (ref "U1") (pin "59") (pinfunction "EVDD_59") (pintype "bidirectional"))
    )
    (net (code "66") (name "unconnected-(IMU1-DROY_M-Pad9)") (class "Default")
      (node (ref "IMU1") (pin "9") (pinfunction "DROY_M_9") (pintype "bidirectional"))
    )
    (net (code "67") (name "unconnected-(IMU1-INT1_A{slash}G-Pad11)") (class "Default")
      (node (ref "IMU1") (pin "11") (pinfunction "INT1_A/G_11") (pintype "bidirectional"))
    )
    (net (code "68") (name "unconnected-(IMU1-INT2_A{slash}G-Pad12)") (class "Default")
      (node (ref "IMU1") (pin "12") (pinfunction "INT2_A/G_12") (pintype "bidirectional"))
    )
    (net (code "69") (name "unconnected-(IMU1-INT_M-Pad10)") (class "Default")
      (node (ref "IMU1") (pin "10") (pinfunction "INT_M_10") (pintype "bidirectional"))
    )
    (net (code "70") (name "unconnected-(J1-Pad2)") (class "Default")
      (node (ref "J1") (pin "2") (pinfunction "2_2") (pintype "passive"))
    )
    (net (code "71") (name "unconnected-(JP2-1-PadDTR)") (class "Default")
      (node (ref "JP2") (pin "DTR") (pinfunction "1_DTR") (pintype "passive"))
    )
    (net (code "72") (name "unconnected-(JP2-4-PadVCC)") (class "Default")
      (node (ref "JP2") (pin "VCC") (pinfunction "4_VCC") (pintype "passive"))
    )
    (net (code "73") (name "unconnected-(JP2-5-PadCTS)") (class "Default")
      (node (ref "JP2") (pin "CTS") (pinfunction "5_CTS") (pintype "passive"))
    )
    (net (code "74") (name "unconnected-(JP9-4-PadVCC)") (class "Default")
      (node (ref "JP9") (pin "VCC") (pinfunction "4_VCC") (pintype "passive"))
    )
    (net (code "75") (name "unconnected-(JP9-5-PadCTS)") (class "Default")
      (node (ref "JP9") (pin "CTS") (pinfunction "5_CTS") (pintype "passive"))
    )
    (net (code "76") (name "unconnected-(U$2-NC{slash}FB-Pad4)") (class "Default")
      (node (ref "U$2") (pin "4") (pinfunction "NC/FB_4") (pintype "passive"))
    )
    (net (code "77") (name "unconnected-(U1-PG3(TOSC2)-Pad17)") (class "Default")
      (node (ref "U1") (pin "17") (pinfunction "PG3(TOSC2)_17") (pintype "bidirectional"))
    )
    (net (code "78") (name "unconnected-(U1-PG4(TOSC1)-Pad18)") (class "Default")
      (node (ref "U1") (pin "18") (pinfunction "PG4(TOSC1)_18") (pintype "bidirectional"))
    )
  )
)
